# Camera_Trigger.net
KiCad netlist of a schematic drawn in EAGLE
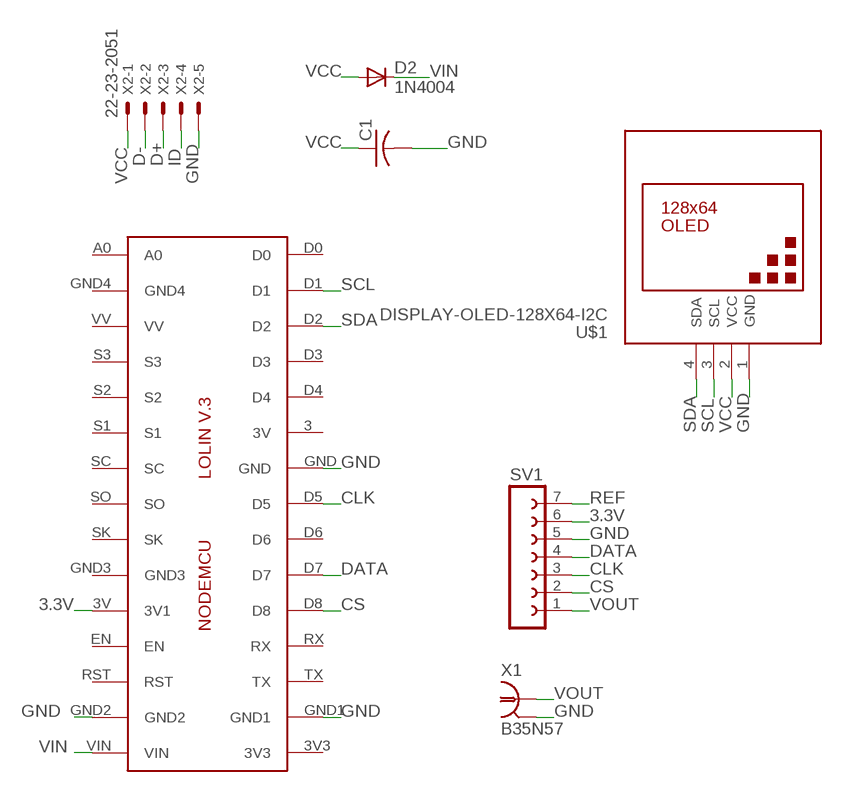
[diagram p0: schematic, sheet 1]

(export (version "E")
  (design (tool "Eeschema 10.0.6"))
  (components
    (comp (ref "C1")
      (value "C-US025-040X050")
      (footprint "eagle-import:C025-040X050")
      (libsource (lib "eagle-import") (part "C-US025-040X050"))
    )
    (comp (ref "D2")
      (value "1N4004")
      (footprint "eagle-import:DO41-10")
      (libsource (lib "eagle-import") (part "1N4004"))
    )
    (comp (ref "IC1")
      (value "LOLINV3")
      (footprint "eagle-import:LOLINV3")
      (libsource (lib "eagle-import") (part "LOLINV3"))
    )
    (comp (ref "SV1")
      (value "FE07-1")
      (footprint "eagle-import:FE07")
      (libsource (lib "eagle-import") (part "FE07-1"))
    )
    (comp (ref "U$1")
      (value "DISPLAY-OLED-128X64-I2C")
      (footprint "eagle-import:DISPLAY-OLED-128X64-I2C")
      (libsource (lib "eagle-import") (part "DISPLAY-OLED-128X64-I2C"))
    )
    (comp (ref "X1")
      (value "B35N57")
      (footprint "eagle-import:B35N57")
      (libsource (lib "eagle-import") (part "B35N57"))
    )
    (comp (ref "X2")
      (value "22-23-2051")
      (footprint "eagle-import:22-23-2051")
      (fields (field (name "MF") "MOLEX"))
      (libsource (lib "eagle-import") (part "22-23-2051"))
    )
  )
  (nets
    (net (code "1") (name "/3.3V") (class "Default")
      (node (ref "IC1") (pin "3V") (pinfunction "3V1_3V") (pintype "bidirectional"))
      (node (ref "SV1") (pin "6") (pinfunction "6_6") (pintype "passive"))
    )
    (net (code "2") (name "/CLK") (class "Default")
      (node (ref "IC1") (pin "D5") (pinfunction "D5_D5") (pintype "bidirectional"))
      (node (ref "SV1") (pin "3") (pinfunction "3_3") (pintype "passive"))
    )
    (net (code "3") (name "/CS") (class "Default")
      (node (ref "IC1") (pin "D8") (pinfunction "D8_D8") (pintype "bidirectional"))
      (node (ref "SV1") (pin "2") (pinfunction "2_2") (pintype "passive"))
    )
    (net (code "4") (name "/D+") (class "Default")
      (node (ref "X2") (pin "3") (pinfunction "S_3") (pintype "passive"))
    )
    (net (code "5") (name "/D-") (class "Default")
      (node (ref "X2") (pin "2") (pinfunction "S_2") (pintype "passive"))
    )
    (net (code "6") (name "/DATA") (class "Default")
      (node (ref "IC1") (pin "D7") (pinfunction "D7_D7") (pintype "bidirectional"))
      (node (ref "SV1") (pin "4") (pinfunction "4_4") (pintype "passive"))
    )
    (net (code "7") (name "/GND") (class "Default")
      (node (ref "C1") (pin "2") (pinfunction "2_2") (pintype "passive"))
      (node (ref "IC1") (pin "GND") (pinfunction "GND_GND") (pintype "bidirectional"))
      (node (ref "IC1") (pin "GND1") (pinfunction "GND1_GND1") (pintype "bidirectional"))
      (node (ref "IC1") (pin "GND2") (pinfunction "GND2_GND2") (pintype "bidirectional"))
      (node (ref "SV1") (pin "5") (pinfunction "5_5") (pintype "passive"))
      (node (ref "U$1") (pin "1") (pinfunction "GND_1") (pintype "power_in"))
      (node (ref "X1") (pin "2") (pinfunction "2_2") (pintype "passive"))
      (node (ref "X1") (pin "3") (pinfunction "2_3") (pintype "passive"))
      (node (ref "X1") (pin "4") (pinfunction "2_4") (pintype "passive"))
      (node (ref "X1") (pin "5") (pinfunction "2_5") (pintype "passive"))
      (node (ref "X2") (pin "5") (pinfunction "S_5") (pintype "passive"))
    )
    (net (code "8") (name "/ID") (class "Default")
      (node (ref "X2") (pin "4") (pinfunction "S_4") (pintype "passive"))
    )
    (net (code "9") (name "/REF") (class "Default")
      (node (ref "SV1") (pin "7") (pinfunction "7_7") (pintype "passive"))
    )
    (net (code "10") (name "/SCL") (class "Default")
      (node (ref "IC1") (pin "D1") (pinfunction "D1_D1") (pintype "bidirectional"))
      (node (ref "U$1") (pin "3") (pinfunction "SCL_3") (pintype "bidirectional"))
    )
    (net (code "11") (name "/SDA") (class "Default")
      (node (ref "IC1") (pin "D2") (pinfunction "D2_D2") (pintype "bidirectional"))
      (node (ref "U$1") (pin "4") (pinfunction "SDA_4") (pintype "bidirectional"))
    )
    (net (code "12") (name "/VCC") (class "Default")
      (node (ref "C1") (pin "1") (pinfunction "1_1") (pintype "passive"))
      (node (ref "D2") (pin "A") (pinfunction "A_A") (pintype "passive"))
      (node (ref "U$1") (pin "2") (pinfunction "VCC_2") (pintype "power_in"))
      (node (ref "X2") (pin "1") (pinfunction "S_1") (pintype "passive"))
    )
    (net (code "13") (name "/VIN") (class "Default")
      (node (ref "D2") (pin "C") (pinfunction "C_C") (pintype "passive"))
      (node (ref "IC1") (pin "VIN") (pinfunction "VIN_VIN") (pintype "bidirectional"))
    )
    (net (code "14") (name "/VOUT") (class "Default")
      (node (ref "SV1") (pin "1") (pinfunction "1_1") (pintype "passive"))
      (node (ref "X1") (pin "1") (pinfunction "1_1") (pintype "passive"))
    )
    (net (code "15") (name "unconnected-(IC1-3V-Pad3)") (class "Default")
      (node (ref "IC1") (pin "3") (pinfunction "3V_3") (pintype "bidirectional"))
    )
    (net (code "16") (name "unconnected-(IC1-Pad3V3)") (class "Default")
      (node (ref "IC1") (pin "3V3") (pinfunction "3V3_3V3") (pintype "bidirectional"))
    )
    (net (code "17") (name "unconnected-(IC1-PadA0)") (class "Default")
      (node (ref "IC1") (pin "A0") (pinfunction "A0_A0") (pintype "bidirectional"))
    )
    (net (code "18") (name "unconnected-(IC1-PadD0)") (class "Default")
      (node (ref "IC1") (pin "D0") (pinfunction "D0_D0") (pintype "bidirectional"))
    )
    (net (code "19") (name "unconnected-(IC1-PadD3)") (class "Default")
      (node (ref "IC1") (pin "D3") (pinfunction "D3_D3") (pintype "bidirectional"))
    )
    (net (code "20") (name "unconnected-(IC1-PadD4)") (class "Default")
      (node (ref "IC1") (pin "D4") (pinfunction "D4_D4") (pintype "bidirectional"))
    )
    (net (code "21") (name "unconnected-(IC1-PadD6)") (class "Default")
      (node (ref "IC1") (pin "D6") (pinfunction "D6_D6") (pintype "bidirectional"))
    )
    (net (code "22") (name "unconnected-(IC1-PadEN)") (class "Default")
      (node (ref "IC1") (pin "EN") (pinfunction "EN_EN") (pintype "bidirectional"))
    )
    (net (code "23") (name "unconnected-(IC1-PadGND3)") (class "Default")
      (node (ref "IC1") (pin "GND3") (pinfunction "GND3_GND3") (pintype "bidirectional"))
    )
    (net (code "24") (name "unconnected-(IC1-PadGND4)") (class "Default")
      (node (ref "IC1") (pin "GND4") (pinfunction "GND4_GND4") (pintype "bidirectional"))
    )
    (net (code "25") (name "unconnected-(IC1-PadRST)") (class "Default")
      (node (ref "IC1") (pin "RST") (pinfunction "RST_RST") (pintype "bidirectional"))
    )
    (net (code "26") (name "unconnected-(IC1-PadRX)") (class "Default")
      (node (ref "IC1") (pin "RX") (pinfunction "RX_RX") (pintype "bidirectional"))
    )
    (net (code "27") (name "unconnected-(IC1-PadS1)") (class "Default")
      (node (ref "IC1") (pin "S1") (pinfunction "S1_S1") (pintype "bidirectional"))
    )
    (net (code "28") (name "unconnected-(IC1-PadS2)") (class "Default")
      (node (ref "IC1") (pin "S2") (pinfunction "S2_S2") (pintype "bidirectional"))
    )
    (net (code "29") (name "unconnected-(IC1-PadS3)") (class "Default")
      (node (ref "IC1") (pin "S3") (pinfunction "S3_S3") (pintype "bidirectional"))
    )
    (net (code "30") (name "unconnected-(IC1-PadSC)") (class "Default")
      (node (ref "IC1") (pin "SC") (pinfunction "SC_SC") (pintype "bidirectional"))
    )
    (net (code "31") (name "unconnected-(IC1-PadSK)") (class "Default")
      (node (ref "IC1") (pin "SK") (pinfunction "SK_SK") (pintype "bidirectional"))
    )
    (net (code "32") (name "unconnected-(IC1-PadSO)") (class "Default")
      (node (ref "IC1") (pin "SO") (pinfunction "SO_SO") (pintype "bidirectional"))
    )
    (net (code "33") (name "unconnected-(IC1-PadTX)") (class "Default")
      (node (ref "IC1") (pin "TX") (pinfunction "TX_TX") (pintype "bidirectional"))
    )
    (net (code "34") (name "unconnected-(IC1-PadVV)") (class "Default")
      (node (ref "IC1") (pin "VV") (pinfunction "VV_VV") (pintype "bidirectional"))
    )
  )
)
